# inverter_interface.net
KiCad netlist of a schematic drawn in EAGLE
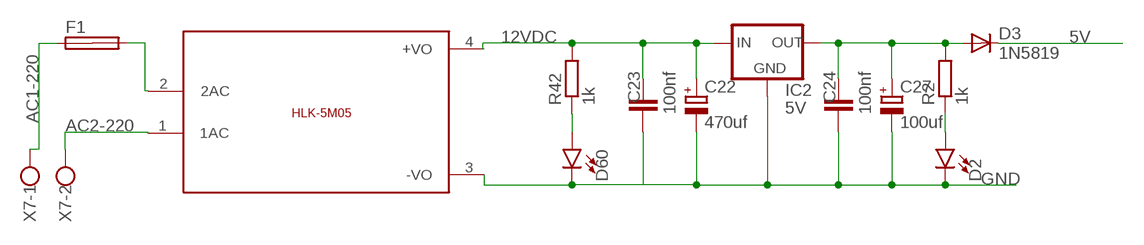
[diagram p0: schematic, sheet 1]
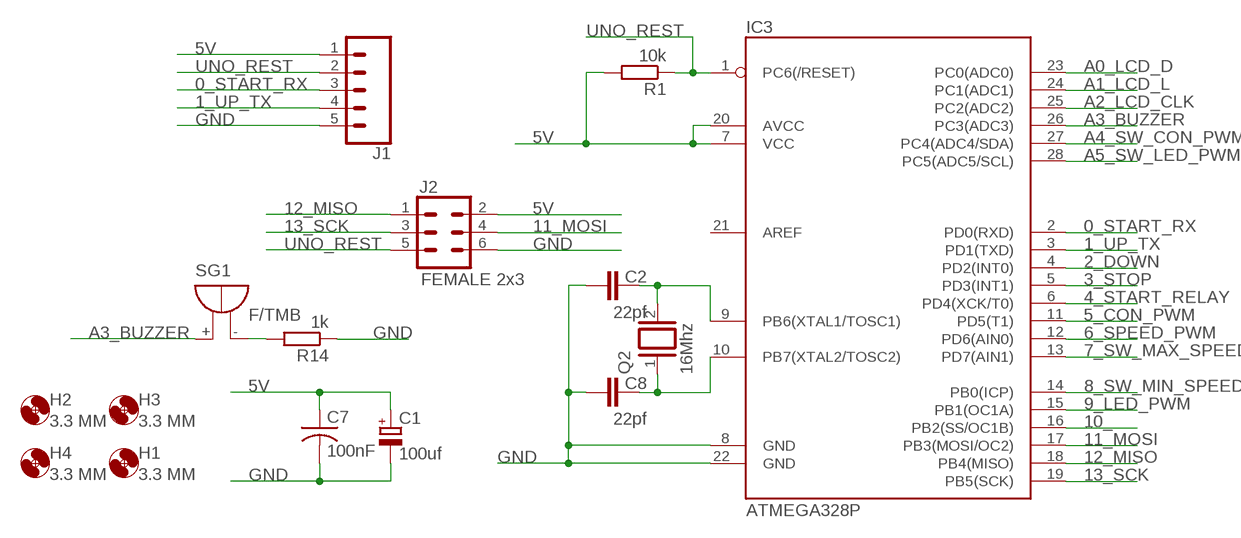
[diagram p1: schematic, sheet 2]
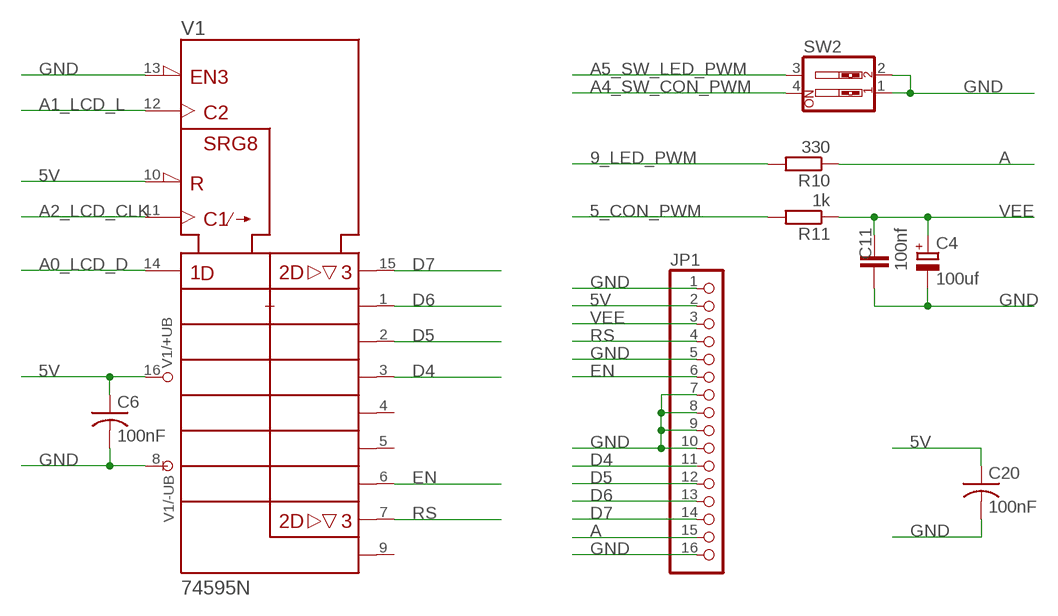
[diagram p2: schematic, sheet 3]
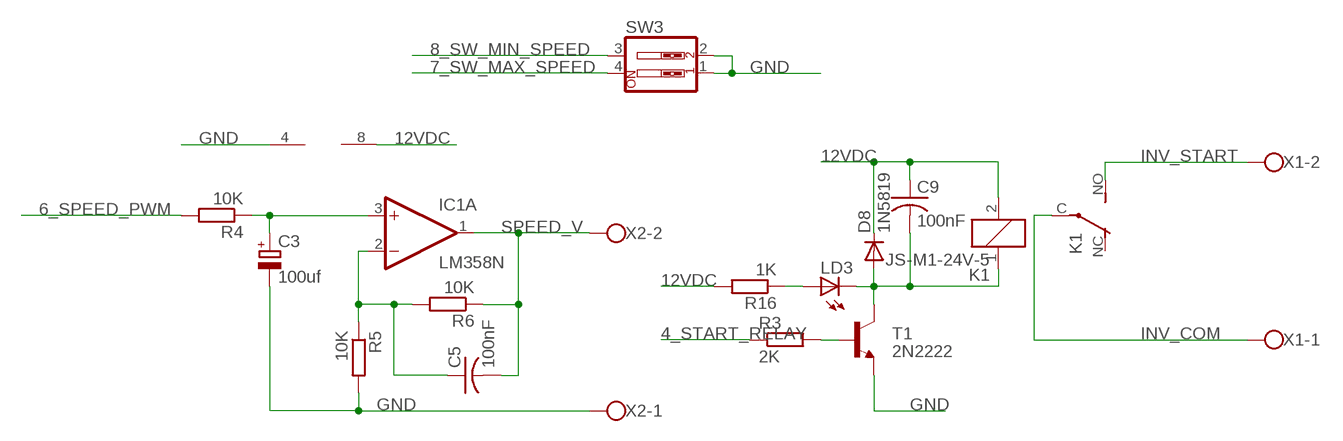
[diagram p3: schematic, sheet 4]
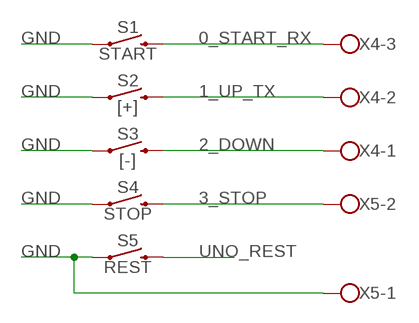
[diagram p4: schematic, sheet 5]

(export (version "E")
  (design (tool "Eeschema 10.0.6"))
  (components
    (comp (ref "C1")
      (value "100uf")
      (footprint "eagle-import:E3,5-8")
      (libsource (lib "eagle-import") (part "CPOL-EUE3.5-8"))
    )
    (comp (ref "C2")
      (value "22pf")
      (footprint "eagle-import:C050-030X075")
      (libsource (lib "eagle-import") (part "C-EU050-030X075"))
    )
    (comp (ref "C7")
      (value "100nF")
      (footprint "eagle-import:C050-035X075")
      (libsource (lib "eagle-import") (part "C-US050-035X075"))
    )
    (comp (ref "C8")
      (value "22pf")
      (footprint "eagle-import:C050-030X075")
      (libsource (lib "eagle-import") (part "C-EU050-030X075"))
    )
    (comp (ref "H1")
      (value "3.3 MM")
      (footprint "eagle-import:3,3")
      (libsource (lib "eagle-import") (part "MOUNT-HOLE3.3"))
    )
    (comp (ref "H2")
      (value "3.3 MM")
      (footprint "eagle-import:3,3")
      (libsource (lib "eagle-import") (part "MOUNT-HOLE3.3"))
    )
    (comp (ref "H3")
      (value "3.3 MM")
      (footprint "eagle-import:3,3")
      (libsource (lib "eagle-import") (part "MOUNT-HOLE3.3"))
    )
    (comp (ref "H4")
      (value "3.3 MM")
      (footprint "eagle-import:3,3")
      (libsource (lib "eagle-import") (part "MOUNT-HOLE3.3"))
    )
    (comp (ref "IC3")
      (value "ATMEGA328P")
      (footprint "eagle-import:DIL-28-3")
      (libsource (lib "eagle-import") (part "ATMEGA328P_PDIP"))
    )
    (comp (ref "J1")
      (value "CONN_05JST-VERT")
      (footprint "eagle-import:JST-5-PTH-VERT")
      (libsource (lib "eagle-import") (part "CONN_05JST-VERT"))
    )
    (comp (ref "J2")
      (value "FEMALE 2x3")
      (footprint "eagle-import:2X3")
      (libsource (lib "eagle-import") (part "CONN_03X2FEMALE"))
    )
    (comp (ref "Q2")
      (value "16Mhz")
      (footprint "eagle-import:QS")
      (libsource (lib "eagle-import") (part "XTAL/S"))
    )
    (comp (ref "R1")
      (value "10k")
      (footprint "eagle-import:0207_10")
      (libsource (lib "eagle-import") (part "R-EU_0207/10"))
    )
    (comp (ref "R14")
      (value "1k")
      (footprint "eagle-import:0207_10")
      (libsource (lib "eagle-import") (part "R-EU_0207/10"))
    )
    (comp (ref "SG1")
      (value "F/TMB")
      (footprint "eagle-import:F_TMB")
      (libsource (lib "eagle-import") (part "F/TMB"))
    )
    (comp (ref "C3")
      (value "100uf")
      (footprint "eagle-import:E3,5-8")
      (libsource (lib "eagle-import") (part "CPOL-EUE3.5-8"))
    )
    (comp (ref "C5")
      (value "100nF")
      (footprint "eagle-import:C050-035X075")
      (libsource (lib "eagle-import") (part "C-US050-035X075"))
    )
    (comp (ref "C9")
      (value "100nF")
      (footprint "eagle-import:C050-035X075")
      (libsource (lib "eagle-import") (part "C-US050-035X075"))
    )
    (comp (ref "D8")
      (value "1N5819")
      (footprint "eagle-import:DO41-10")
      (libsource (lib "eagle-import") (part "1N4004"))
    )
    (comp (ref "IC1")
      (value "LM358N")
      (footprint "eagle-import:DIL08")
      (libsource (lib "eagle-import") (part "LM358N"))
    )
    (comp (ref "K1")
      (value "JS-M1-24V-5")
      (footprint "eagle-import:JS-M")
      (fields (field (name "MF") "FARNELL") (field (name "MPN") "JSM1-12V-5"))
      (libsource (lib "eagle-import") (part "JS-M1-12V-5"))
    )
    (comp (ref "LD3")
      (value "LED5MM")
      (footprint "eagle-import:LED5MM")
      (libsource (lib "eagle-import") (part "led_LED5MM"))
    )
    (comp (ref "R3")
      (value "2K")
      (footprint "eagle-import:0207_10")
      (libsource (lib "eagle-import") (part "rcl-2_R-EU_0207/10"))
    )
    (comp (ref "R4")
      (value "10K")
      (footprint "eagle-import:0207_10")
      (libsource (lib "eagle-import") (part "rcl-2_R-EU_0207/10"))
    )
    (comp (ref "R5")
      (value "10K")
      (footprint "eagle-import:0207_10")
      (libsource (lib "eagle-import") (part "rcl-2_R-EU_0207/10"))
    )
    (comp (ref "R6")
      (value "10K")
      (footprint "eagle-import:0207_10")
      (libsource (lib "eagle-import") (part "rcl-2_R-EU_0207/10"))
    )
    (comp (ref "R16")
      (value "1K")
      (footprint "eagle-import:0207_10")
      (libsource (lib "eagle-import") (part "rcl-2_R-EU_0207/10"))
    )
    (comp (ref "SW3")
      (value "SW_DIP-2")
      (footprint "eagle-import:DIPSWITCH-02")
      (libsource (lib "eagle-import") (part "SW_DIP-2"))
    )
    (comp (ref "T1")
      (value "2N2222")
      (footprint "eagle-import:TO92-EBC-OVAL")
      (libsource (lib "eagle-import") (part "2N2222"))
    )
    (comp (ref "X1")
      (value "W237-102")
      (footprint "eagle-import:W237-102")
      (fields (field (name "MPN") "237-102"))
      (libsource (lib "eagle-import") (part "con-wago-500_195_W237-102"))
    )
    (comp (ref "X2")
      (value "W237-102")
      (footprint "eagle-import:W237-102")
      (fields (field (name "MPN") "237-102"))
      (libsource (lib "eagle-import") (part "con-wago-500_195_W237-102"))
    )
    (comp (ref "C4")
      (value "100uf")
      (footprint "eagle-import:E3,5-8")
      (libsource (lib "eagle-import") (part "CPOL-EUE3.5-8"))
    )
    (comp (ref "C6")
      (value "100nF")
      (footprint "eagle-import:C050-035X075")
      (libsource (lib "eagle-import") (part "C-US050-035X075"))
    )
    (comp (ref "C11")
      (value "100nf")
      (footprint "eagle-import:C050-030X075")
      (libsource (lib "eagle-import") (part "C-EU050-030X075"))
    )
    (comp (ref "C20")
      (value "100nF")
      (footprint "eagle-import:C050-035X075")
      (libsource (lib "eagle-import") (part "C-US050-035X075"))
    )
    (comp (ref "JP1")
      (value "PINHD-1X16")
      (footprint "eagle-import:1X16")
      (libsource (lib "eagle-import") (part "PINHD-1X16"))
    )
    (comp (ref "R10")
      (value "330")
      (footprint "eagle-import:0207_10")
      (libsource (lib "eagle-import") (part "R-EU_0207/10"))
    )
    (comp (ref "R11")
      (value "1k")
      (footprint "eagle-import:0207_10")
      (libsource (lib "eagle-import") (part "R-EU_0207/10"))
    )
    (comp (ref "SW2")
      (value "SW_DIP-2")
      (footprint "eagle-import:DIPSWITCH-02")
      (libsource (lib "eagle-import") (part "SW_DIP-2"))
    )
    (comp (ref "V1")
      (value "74595N")
      (footprint "eagle-import:DIL16")
      (libsource (lib "eagle-import") (part "74595N"))
    )
    (comp (ref "S1")
      (value "START")
      (footprint "eagle-import:TACTILE_SWITCH_PTH_6.0MM")
      (libsource (lib "eagle-import") (part "MOMENTARY-SWITCH-SPST-PTH-6.0MM"))
    )
    (comp (ref "S2")
      (value "[+]")
      (footprint "eagle-import:TACTILE_SWITCH_PTH_6.0MM")
      (libsource (lib "eagle-import") (part "MOMENTARY-SWITCH-SPST-PTH-6.0MM"))
    )
    (comp (ref "S3")
      (value "[-]")
      (footprint "eagle-import:TACTILE_SWITCH_PTH_6.0MM")
      (libsource (lib "eagle-import") (part "MOMENTARY-SWITCH-SPST-PTH-6.0MM"))
    )
    (comp (ref "S4")
      (value "STOP")
      (footprint "eagle-import:TACTILE_SWITCH_PTH_6.0MM")
      (libsource (lib "eagle-import") (part "MOMENTARY-SWITCH-SPST-PTH-6.0MM"))
    )
    (comp (ref "S5")
      (value "REST")
      (footprint "eagle-import:TACTILE_SWITCH_PTH_6.0MM")
      (libsource (lib "eagle-import") (part "MOMENTARY-SWITCH-SPST-PTH-6.0MM"))
    )
    (comp (ref "X4")
      (value "W237-103")
      (footprint "eagle-import:W237-103")
      (fields (field (name "MPN") "237-103"))
      (libsource (lib "eagle-import") (part "W237-103"))
    )
    (comp (ref "X5")
      (value "W237-102")
      (footprint "eagle-import:W237-102")
      (fields (field (name "MPN") "237-102"))
      (libsource (lib "eagle-import") (part "con-wago-500_195_W237-102"))
    )
    (comp (ref "C22")
      (value "470uf")
      (footprint "eagle-import:E3,5-8")
      (libsource (lib "eagle-import") (part "CPOL-EUE3.5-8"))
    )
    (comp (ref "C23")
      (value "100nf")
      (footprint "eagle-import:C050-030X075")
      (libsource (lib "eagle-import") (part "C-EU050-030X075"))
    )
    (comp (ref "C24")
      (value "100nf")
      (footprint "eagle-import:C050-030X075")
      (libsource (lib "eagle-import") (part "C-EU050-030X075"))
    )
    (comp (ref "C27")
      (value "100uf")
      (footprint "eagle-import:E3,5-8")
      (libsource (lib "eagle-import") (part "CPOL-EUE3.5-8"))
    )
    (comp (ref "D2")
      (value "LED5MM")
      (footprint "eagle-import:LED_5MM")
      (libsource (lib "eagle-import") (part "LED5MM"))
    )
    (comp (ref "D3")
      (value "1N5819")
      (footprint "eagle-import:DO41-10")
      (libsource (lib "eagle-import") (part "1N4004"))
    )
    (comp (ref "D60")
      (value "LED5MM")
      (footprint "eagle-import:LED_5MM")
      (libsource (lib "eagle-import") (part "LED5MM"))
    )
    (comp (ref "F1")
      (value "SHK20Q")
      (footprint "eagle-import:SHK20Q")
      (libsource (lib "eagle-import") (part "SHK20Q"))
    )
    (comp (ref "IC2")
      (value "5V")
      (footprint "eagle-import:78XXL")
      (libsource (lib "eagle-import") (part "V_REG_78XXSIDE"))
    )
    (comp (ref "R2")
      (value "1k")
      (footprint "eagle-import:0207_10")
      (libsource (lib "eagle-import") (part "R-EU_0207/10"))
    )
    (comp (ref "R42")
      (value "1k")
      (footprint "eagle-import:0207_10")
      (libsource (lib "eagle-import") (part "R-EU_0207/10"))
    )
    (comp (ref "U$3")
      (value "5VDC/5W")
      (footprint "eagle-import:HLK-5M05")
      (libsource (lib "eagle-import") (part "HLK-5M05"))
    )
    (comp (ref "X7")
      (value "W237-102")
      (footprint "eagle-import:W237-102")
      (libsource (lib "eagle-import") (part "W237-102"))
    )
  )
  (nets
    (net (code "1") (name "0_START_RX") (class "Default")
      (node (ref "IC3") (pin "2") (pinfunction "PD0(RXD)_2") (pintype "bidirectional"))
      (node (ref "J1") (pin "3") (pinfunction "3_3") (pintype "passive"))
      (node (ref "S1") (pin "3") (pinfunction "2_3") (pintype "passive"))
      (node (ref "X4") (pin "3") (pinfunction "KL_3") (pintype "passive"))
    )
    (net (code "2") (name "1_UP_TX") (class "Default")
      (node (ref "IC3") (pin "3") (pinfunction "PD1(TXD)_3") (pintype "bidirectional"))
      (node (ref "J1") (pin "4") (pinfunction "4_4") (pintype "passive"))
      (node (ref "S2") (pin "3") (pinfunction "2_3") (pintype "passive"))
      (node (ref "X4") (pin "2") (pinfunction "KL_2") (pintype "passive"))
    )
    (net (code "3") (name "2_DOWN") (class "Default")
      (node (ref "IC3") (pin "4") (pinfunction "PD2(INT0)_4") (pintype "bidirectional"))
      (node (ref "S3") (pin "3") (pinfunction "2_3") (pintype "passive"))
      (node (ref "X4") (pin "1") (pinfunction "KL_1") (pintype "passive"))
    )
    (net (code "4") (name "3_STOP") (class "Default")
      (node (ref "IC3") (pin "5") (pinfunction "PD3(INT1)_5") (pintype "bidirectional"))
      (node (ref "S4") (pin "3") (pinfunction "2_3") (pintype "passive"))
      (node (ref "X5") (pin "2") (pinfunction "KL_2") (pintype "passive"))
    )
    (net (code "5") (name "4_START_RELAY") (class "Default")
      (node (ref "IC3") (pin "6") (pinfunction "PD4(XCK/T0)_6") (pintype "bidirectional"))
      (node (ref "R3") (pin "1") (pinfunction "1_1") (pintype "passive"))
    )
    (net (code "6") (name "5V") (class "Default")
      (node (ref "C1") (pin "+") (pinfunction "+_+") (pintype "passive"))
      (node (ref "C20") (pin "1") (pinfunction "1_1") (pintype "passive"))
      (node (ref "C6") (pin "1") (pinfunction "1_1") (pintype "passive"))
      (node (ref "C7") (pin "1") (pinfunction "1_1") (pintype "passive"))
      (node (ref "D3") (pin "C") (pinfunction "C_C") (pintype "passive"))
      (node (ref "IC3") (pin "20") (pinfunction "AVCC_20") (pintype "bidirectional"))
      (node (ref "IC3") (pin "7") (pinfunction "VCC_7") (pintype "bidirectional"))
      (node (ref "J1") (pin "1") (pinfunction "1_1") (pintype "passive"))
      (node (ref "J2") (pin "2") (pinfunction "2_2") (pintype "bidirectional"))
      (node (ref "JP1") (pin "2") (pinfunction "2_2") (pintype "passive"))
      (node (ref "R1") (pin "2") (pinfunction "2_2") (pintype "passive"))
      (node (ref "V1") (pin "10") (pinfunction "~{SRCLR}_10") (pintype "input"))
      (node (ref "V1") (pin "16") (pinfunction "+UB_16") (pintype "power_in"))
    )
    (net (code "7") (name "5_CON_PWM") (class "Default")
      (node (ref "IC3") (pin "11") (pinfunction "PD5(T1)_11") (pintype "bidirectional"))
      (node (ref "R11") (pin "2") (pinfunction "2_2") (pintype "passive"))
    )
    (net (code "8") (name "6_SPEED_PWM") (class "Default")
      (node (ref "IC3") (pin "12") (pinfunction "PD6(AIN0)_12") (pintype "bidirectional"))
      (node (ref "R4") (pin "2") (pinfunction "2_2") (pintype "passive"))
    )
    (net (code "9") (name "7_SW_MAX_SPEED") (class "Default")
      (node (ref "IC3") (pin "13") (pinfunction "PD7(AIN1)_13") (pintype "bidirectional"))
      (node (ref "SW3") (pin "4") (pinfunction "4_4") (pintype "passive"))
    )
    (net (code "10") (name "8_SW_MIN_SPEED") (class "Default")
      (node (ref "IC3") (pin "14") (pinfunction "PB0(ICP)_14") (pintype "bidirectional"))
      (node (ref "SW3") (pin "3") (pinfunction "3_3") (pintype "passive"))
    )
    (net (code "11") (name "9_LED_PWM") (class "Default")
      (node (ref "IC3") (pin "15") (pinfunction "PB1(OC1A)_15") (pintype "bidirectional"))
      (node (ref "R10") (pin "2") (pinfunction "2_2") (pintype "passive"))
    )
    (net (code "12") (name "10_") (class "Default")
      (node (ref "IC3") (pin "16") (pinfunction "PB2(SS/OC1B)_16") (pintype "bidirectional"))
    )
    (net (code "13") (name "11_MOSI") (class "Default")
      (node (ref "IC3") (pin "17") (pinfunction "PB3(MOSI/OC2)_17") (pintype "bidirectional"))
      (node (ref "J2") (pin "4") (pinfunction "4_4") (pintype "bidirectional"))
    )
    (net (code "14") (name "12VDC") (class "Default")
      (node (ref "C22") (pin "+") (pinfunction "+_+") (pintype "passive"))
      (node (ref "C23") (pin "2") (pinfunction "2_2") (pintype "passive"))
      (node (ref "C9") (pin "1") (pinfunction "1_1") (pintype "passive"))
      (node (ref "D8") (pin "C") (pinfunction "C_C") (pintype "passive"))
      (node (ref "IC1") (pin "8") (pinfunction "V+_8") (pintype "power_in"))
      (node (ref "IC2") (pin "IN") (pinfunction "IN_IN") (pintype "input"))
      (node (ref "K1") (pin "2") (pinfunction "2_2") (pintype "passive"))
      (node (ref "R16") (pin "2") (pinfunction "2_2") (pintype "passive"))
      (node (ref "R42") (pin "2") (pinfunction "2_2") (pintype "passive"))
      (node (ref "U$3") (pin "4") (pinfunction "+VO_4") (pintype "bidirectional"))
    )
    (net (code "15") (name "12_MISO") (class "Default")
      (node (ref "IC3") (pin "18") (pinfunction "PB4(MISO)_18") (pintype "bidirectional"))
      (node (ref "J2") (pin "1") (pinfunction "1_1") (pintype "bidirectional"))
    )
    (net (code "16") (name "13_SCK") (class "Default")
      (node (ref "IC3") (pin "19") (pinfunction "PB5(SCK)_19") (pintype "bidirectional"))
      (node (ref "J2") (pin "3") (pinfunction "3_3") (pintype "bidirectional"))
    )
    (net (code "17") (name "A") (class "Default")
      (node (ref "JP1") (pin "15") (pinfunction "15_15") (pintype "passive"))
      (node (ref "R10") (pin "1") (pinfunction "1_1") (pintype "passive"))
    )
    (net (code "18") (name "A0_LCD_D") (class "Default")
      (node (ref "IC3") (pin "23") (pinfunction "PC0(ADC0)_23") (pintype "bidirectional"))
      (node (ref "V1") (pin "14") (pinfunction "SER_14") (pintype "input"))
    )
    (net (code "19") (name "A1_LCD_L") (class "Default")
      (node (ref "IC3") (pin "24") (pinfunction "PC1(ADC1)_24") (pintype "bidirectional"))
      (node (ref "V1") (pin "12") (pinfunction "RCK_12") (pintype "input"))
    )
    (net (code "20") (name "A2_LCD_CLK") (class "Default")
      (node (ref "IC3") (pin "25") (pinfunction "PC2(ADC2)_25") (pintype "bidirectional"))
      (node (ref "V1") (pin "11") (pinfunction "SRCK_11") (pintype "input"))
    )
    (net (code "21") (name "A3_BUZZER") (class "Default")
      (node (ref "IC3") (pin "26") (pinfunction "PC3(ADC3)_26") (pintype "bidirectional"))
      (node (ref "SG1") (pin "+") (pinfunction "+_+") (pintype "passive"))
    )
    (net (code "22") (name "A4_SW_CON_PWM") (class "Default")
      (node (ref "IC3") (pin "27") (pinfunction "PC4(ADC4/SDA)_27") (pintype "bidirectional"))
      (node (ref "SW2") (pin "4") (pinfunction "4_4") (pintype "passive"))
    )
    (net (code "23") (name "A5_SW_LED_PWM") (class "Default")
      (node (ref "IC3") (pin "28") (pinfunction "PC5(ADC5/SCL)_28") (pintype "bidirectional"))
      (node (ref "SW2") (pin "3") (pinfunction "3_3") (pintype "passive"))
    )
    (net (code "24") (name "AC1-220") (class "Default")
      (node (ref "F1") (pin "1A") (pinfunction "1A_1A") (pintype "passive"))
      (node (ref "X7") (pin "1") (pinfunction "KL_1") (pintype "passive"))
    )
    (net (code "25") (name "AC2-220") (class "Default")
      (node (ref "U$3") (pin "1") (pinfunction "1AC_1") (pintype "bidirectional"))
      (node (ref "X7") (pin "2") (pinfunction "KL_2") (pintype "passive"))
    )
    (net (code "26") (name "D4") (class "Default")
      (node (ref "JP1") (pin "11") (pinfunction "11_11") (pintype "passive"))
      (node (ref "V1") (pin "3") (pinfunction "QD_3") (pintype "tri_state"))
    )
    (net (code "27") (name "D5") (class "Default")
      (node (ref "JP1") (pin "12") (pinfunction "12_12") (pintype "passive"))
      (node (ref "V1") (pin "2") (pinfunction "QC_2") (pintype "tri_state"))
    )
    (net (code "28") (name "D6") (class "Default")
      (node (ref "JP1") (pin "13") (pinfunction "13_13") (pintype "passive"))
      (node (ref "V1") (pin "1") (pinfunction "QB_1") (pintype "tri_state"))
    )
    (net (code "29") (name "D7") (class "Default")
      (node (ref "JP1") (pin "14") (pinfunction "14_14") (pintype "passive"))
      (node (ref "V1") (pin "15") (pinfunction "QA_15") (pintype "tri_state"))
    )
    (net (code "30") (name "EN") (class "Default")
      (node (ref "JP1") (pin "6") (pinfunction "6_6") (pintype "passive"))
      (node (ref "V1") (pin "6") (pinfunction "QG_6") (pintype "tri_state"))
    )
    (net (code "31") (name "GND") (class "Default")
      (node (ref "C1") (pin "-") (pinfunction "-_-") (pintype "passive"))
      (node (ref "C11") (pin "1") (pinfunction "1_1") (pintype "passive"))
      (node (ref "C2") (pin "1") (pinfunction "1_1") (pintype "passive"))
      (node (ref "C20") (pin "2") (pinfunction "2_2") (pintype "passive"))
      (node (ref "C22") (pin "-") (pinfunction "-_-") (pintype "passive"))
      (node (ref "C23") (pin "1") (pinfunction "1_1") (pintype "passive"))
      (node (ref "C24") (pin "1") (pinfunction "1_1") (pintype "passive"))
      (node (ref "C27") (pin "-") (pinfunction "-_-") (pintype "passive"))
      (node (ref "C3") (pin "-") (pinfunction "-_-") (pintype "passive"))
      (node (ref "C4") (pin "-") (pinfunction "-_-") (pintype "passive"))
      (node (ref "C6") (pin "2") (pinfunction "2_2") (pintype "passive"))
      (node (ref "C7") (pin "2") (pinfunction "2_2") (pintype "passive"))
      (node (ref "C8") (pin "1") (pinfunction "1_1") (pintype "passive"))
      (node (ref "D2") (pin "K") (pinfunction "C_K") (pintype "passive"))
      (node (ref "D60") (pin "K") (pinfunction "C_K") (pintype "passive"))
      (node (ref "IC1") (pin "4") (pinfunction "V-_4") (pintype "power_in"))
      (node (ref "IC2") (pin "GND") (pinfunction "GND_GND") (pintype "input"))
      (node (ref "IC3") (pin "22") (pinfunction "GND_22") (pintype "bidirectional"))
      (node (ref "IC3") (pin "8") (pinfunction "GND_8") (pintype "bidirectional"))
      (node (ref "J1") (pin "5") (pinfunction "5_5") (pintype "passive"))
      (node (ref "J2") (pin "6") (pinfunction "6_6") (pintype "bidirectional"))
      (node (ref "JP1") (pin "1") (pinfunction "1_1") (pintype "passive"))
      (node (ref "JP1") (pin "10") (pinfunction "10_10") (pintype "passive"))
      (node (ref "JP1") (pin "16") (pinfunction "16_16") (pintype "passive"))
      (node (ref "JP1") (pin "5") (pinfunction "5_5") (pintype "passive"))
      (node (ref "JP1") (pin "7") (pinfunction "7_7") (pintype "passive"))
      (node (ref "JP1") (pin "8") (pinfunction "8_8") (pintype "passive"))
      (node (ref "JP1") (pin "9") (pinfunction "9_9") (pintype "passive"))
      (node (ref "R14") (pin "1") (pinfunction "1_1") (pintype "passive"))
      (node (ref "R5") (pin "2") (pinfunction "2_2") (pintype "passive"))
      (node (ref "S1") (pin "1") (pinfunction "1_1") (pintype "passive"))
      (node (ref "S2") (pin "1") (pinfunction "1_1") (pintype "passive"))
      (node (ref "S3") (pin "1") (pinfunction "1_1") (pintype "passive"))
      (node (ref "S4") (pin "1") (pinfunction "1_1") (pintype "passive"))
      (node (ref "S5") (pin "1") (pinfunction "1_1") (pintype "passive"))
      (node (ref "SW2") (pin "1") (pinfunction "1_1") (pintype "passive"))
      (node (ref "SW2") (pin "2") (pinfunction "2_2") (pintype "passive"))
      (node (ref "SW3") (pin "1") (pinfunction "1_1") (pintype "passive"))
      (node (ref "SW3") (pin "2") (pinfunction "2_2") (pintype "passive"))
      (node (ref "T1") (pin "E") (pinfunction "E_E") (pintype "passive"))
      (node (ref "U$3") (pin "3") (pinfunction "-VO_3") (pintype "bidirectional"))
      (node (ref "V1") (pin "13") (pinfunction "~{G}_13") (pintype "input"))
      (node (ref "V1") (pin "8") (pinfunction "-UB_8") (pintype "power_in"))
      (node (ref "X2") (pin "1") (pinfunction "KL_1") (pintype "passive"))
      (node (ref "X5") (pin "1") (pinfunction "KL_1") (pintype "passive"))
    )
    (net (code "32") (name "INV_COM") (class "Default")
      (node (ref "K1") (pin "C") (pinfunction "P_C") (pintype "passive"))
      (node (ref "X1") (pin "1") (pinfunction "KL_1") (pintype "passive"))
    )
    (net (code "33") (name "INV_START") (class "Default")
      (node (ref "K1") (pin "NO") (pinfunction "S_NO") (pintype "passive"))
      (node (ref "X1") (pin "2") (pinfunction "KL_2") (pintype "passive"))
    )
    (net (code "34") (name "Net-(C24-Pad2)") (class "Default")
      (node (ref "C24") (pin "2") (pinfunction "2_2") (pintype "passive"))
      (node (ref "C27") (pin "+") (pinfunction "+_+") (pintype "passive"))
      (node (ref "D3") (pin "A") (pinfunction "A_A") (pintype "passive"))
      (node (ref "IC2") (pin "OUT") (pinfunction "OUT_OUT") (pintype "output"))
      (node (ref "R2") (pin "2") (pinfunction "2_2") (pintype "passive"))
    )
    (net (code "35") (name "Net-(D2-PadA)") (class "Default")
      (node (ref "D2") (pin "A") (pinfunction "A_A") (pintype "passive"))
      (node (ref "R2") (pin "1") (pinfunction "1_1") (pintype "passive"))
    )
    (net (code "36") (name "Net-(D60-PadA)") (class "Default")
      (node (ref "D60") (pin "A") (pinfunction "A_A") (pintype "passive"))
      (node (ref "R42") (pin "1") (pinfunction "1_1") (pintype "passive"))
    )
    (net (code "37") (name "Net-(IC1A-+IN)") (class "Default")
      (node (ref "C3") (pin "+") (pinfunction "+_+") (pintype "passive"))
      (node (ref "IC1") (pin "3") (pinfunction "+IN_3") (pintype "input"))
      (node (ref "R4") (pin "1") (pinfunction "1_1") (pintype "passive"))
    )
    (net (code "38") (name "Net-(IC1A--IN)") (class "Default")
      (node (ref "C5") (pin "1") (pinfunction "1_1") (pintype "passive"))
      (node (ref "IC1") (pin "2") (pinfunction "-IN_2") (pintype "input"))
      (node (ref "R5") (pin "1") (pinfunction "1_1") (pintype "passive"))
      (node (ref "R6") (pin "2") (pinfunction "2_2") (pintype "passive"))
    )
    (net (code "39") (name "Net-(IC3-PB6(XTAL1{slash}TOSC1))") (class "Default")
      (node (ref "C2") (pin "2") (pinfunction "2_2") (pintype "passive"))
      (node (ref "IC3") (pin "9") (pinfunction "PB6(XTAL1/TOSC1)_9") (pintype "bidirectional"))
      (node (ref "Q2") (pin "2") (pinfunction "2_2") (pintype "passive"))
    )
    (net (code "40") (name "Net-(IC3-PB7(XTAL2{slash}TOSC2))") (class "Default")
      (node (ref "C8") (pin "2") (pinfunction "2_2") (pintype "passive"))
      (node (ref "IC3") (pin "10") (pinfunction "PB7(XTAL2/TOSC2)_10") (pintype "bidirectional"))
      (node (ref "Q2") (pin "1") (pinfunction "1_1") (pintype "passive"))
    )
    (net (code "41") (name "Net-(LD3-C)") (class "Default")
      (node (ref "C9") (pin "2") (pinfunction "2_2") (pintype "passive"))
      (node (ref "D8") (pin "A") (pinfunction "A_A") (pintype "passive"))
      (node (ref "K1") (pin "1") (pinfunction "1_1") (pintype "passive"))
      (node (ref "LD3") (pin "K") (pinfunction "C_K") (pintype "passive"))
      (node (ref "T1") (pin "C") (pinfunction "C_C") (pintype "passive"))
    )
    (net (code "42") (name "Net-(LD3-PadA)") (class "Default")
      (node (ref "LD3") (pin "A") (pinfunction "A_A") (pintype "passive"))
      (node (ref "R16") (pin "1") (pinfunction "1_1") (pintype "passive"))
    )
    (net (code "43") (name "Net-(R3-Pad2)") (class "Default")
      (node (ref "R3") (pin "2") (pinfunction "2_2") (pintype "passive"))
      (node (ref "T1") (pin "B") (pinfunction "B_B") (pintype "passive"))
    )
    (net (code "44") (name "Net-(R14-Pad2)") (class "Default")
      (node (ref "R14") (pin "2") (pinfunction "2_2") (pintype "passive"))
      (node (ref "SG1") (pin "-") (pinfunction "-_-") (pintype "passive"))
    )
    (net (code "45") (name "Net-(U$3-2AC)") (class "Default")
      (node (ref "F1") (pin "2A") (pinfunction "2A_2A") (pintype "passive"))
      (node (ref "U$3") (pin "2") (pinfunction "2AC_2") (pintype "bidirectional"))
    )
    (net (code "46") (name "RS") (class "Default")
      (node (ref "JP1") (pin "4") (pinfunction "4_4") (pintype "passive"))
      (node (ref "V1") (pin "7") (pinfunction "QH_7") (pintype "tri_state"))
    )
    (net (code "47") (name "SPEED_V") (class "Default")
      (node (ref "C5") (pin "2") (pinfunction "2_2") (pintype "passive"))
      (node (ref "IC1") (pin "1") (pinfunction "OUT_1") (pintype "output"))
      (node (ref "R6") (pin "1") (pinfunction "1_1") (pintype "passive"))
      (node (ref "X2") (pin "2") (pinfunction "KL_2") (pintype "passive"))
    )
    (net (code "48") (name "UNO_REST") (class "Default")
      (node (ref "IC3") (pin "1") (pinfunction "PC6(/RESET)_1") (pintype "bidirectional"))
      (node (ref "J1") (pin "2") (pinfunction "2_2") (pintype "passive"))
      (node (ref "J2") (pin "5") (pinfunction "5_5") (pintype "bidirectional"))
      (node (ref "R1") (pin "1") (pinfunction "1_1") (pintype "passive"))
      (node (ref "S5") (pin "3") (pinfunction "2_3") (pintype "passive"))
    )
    (net (code "49") (name "VEE") (class "Default")
      (node (ref "C11") (pin "2") (pinfunction "2_2") (pintype "passive"))
      (node (ref "C4") (pin "+") (pinfunction "+_+") (pintype "passive"))
      (node (ref "JP1") (pin "3") (pinfunction "3_3") (pintype "passive"))
      (node (ref "R11") (pin "1") (pinfunction "1_1") (pintype "passive"))
    )
    (net (code "50") (name "unconnected-(F1-Pad1B)") (class "Default")
      (node (ref "F1") (pin "1B") (pinfunction "1B_1B") (pintype "passive"))
    )
    (net (code "51") (name "unconnected-(F1-Pad2B)") (class "Default")
      (node (ref "F1") (pin "2B") (pinfunction "2B_2B") (pintype "passive"))
    )
    (net (code "52") (name "unconnected-(IC3-AREF-Pad21)") (class "Default")
      (node (ref "IC3") (pin "21") (pinfunction "AREF_21") (pintype "bidirectional"))
    )
    (net (code "53") (name "unconnected-(K1B-O-PadNC)") (class "Default")
      (node (ref "K1") (pin "NC") (pinfunction "O_NC") (pintype "passive"))
    )
    (net (code "54") (name "unconnected-(V1C-QE-Pad4)") (class "Default")
      (node (ref "V1") (pin "4") (pinfunction "QE_4") (pintype "tri_state"))
    )
    (net (code "55") (name "unconnected-(V1C-QF-Pad5)") (class "Default")
      (node (ref "V1") (pin "5") (pinfunction "QF_5") (pintype "tri_state"))
    )
    (net (code "56") (name "unconnected-(V1C-QH*-Pad9)") (class "Default")
      (node (ref "V1") (pin "9") (pinfunction "QH*_9") (pintype "output"))
    )
  )
)
